# AIRZAI_BASE_BD_REVA_Sheet1.net
KiCad netlist of a schematic drawn in Altium Designer
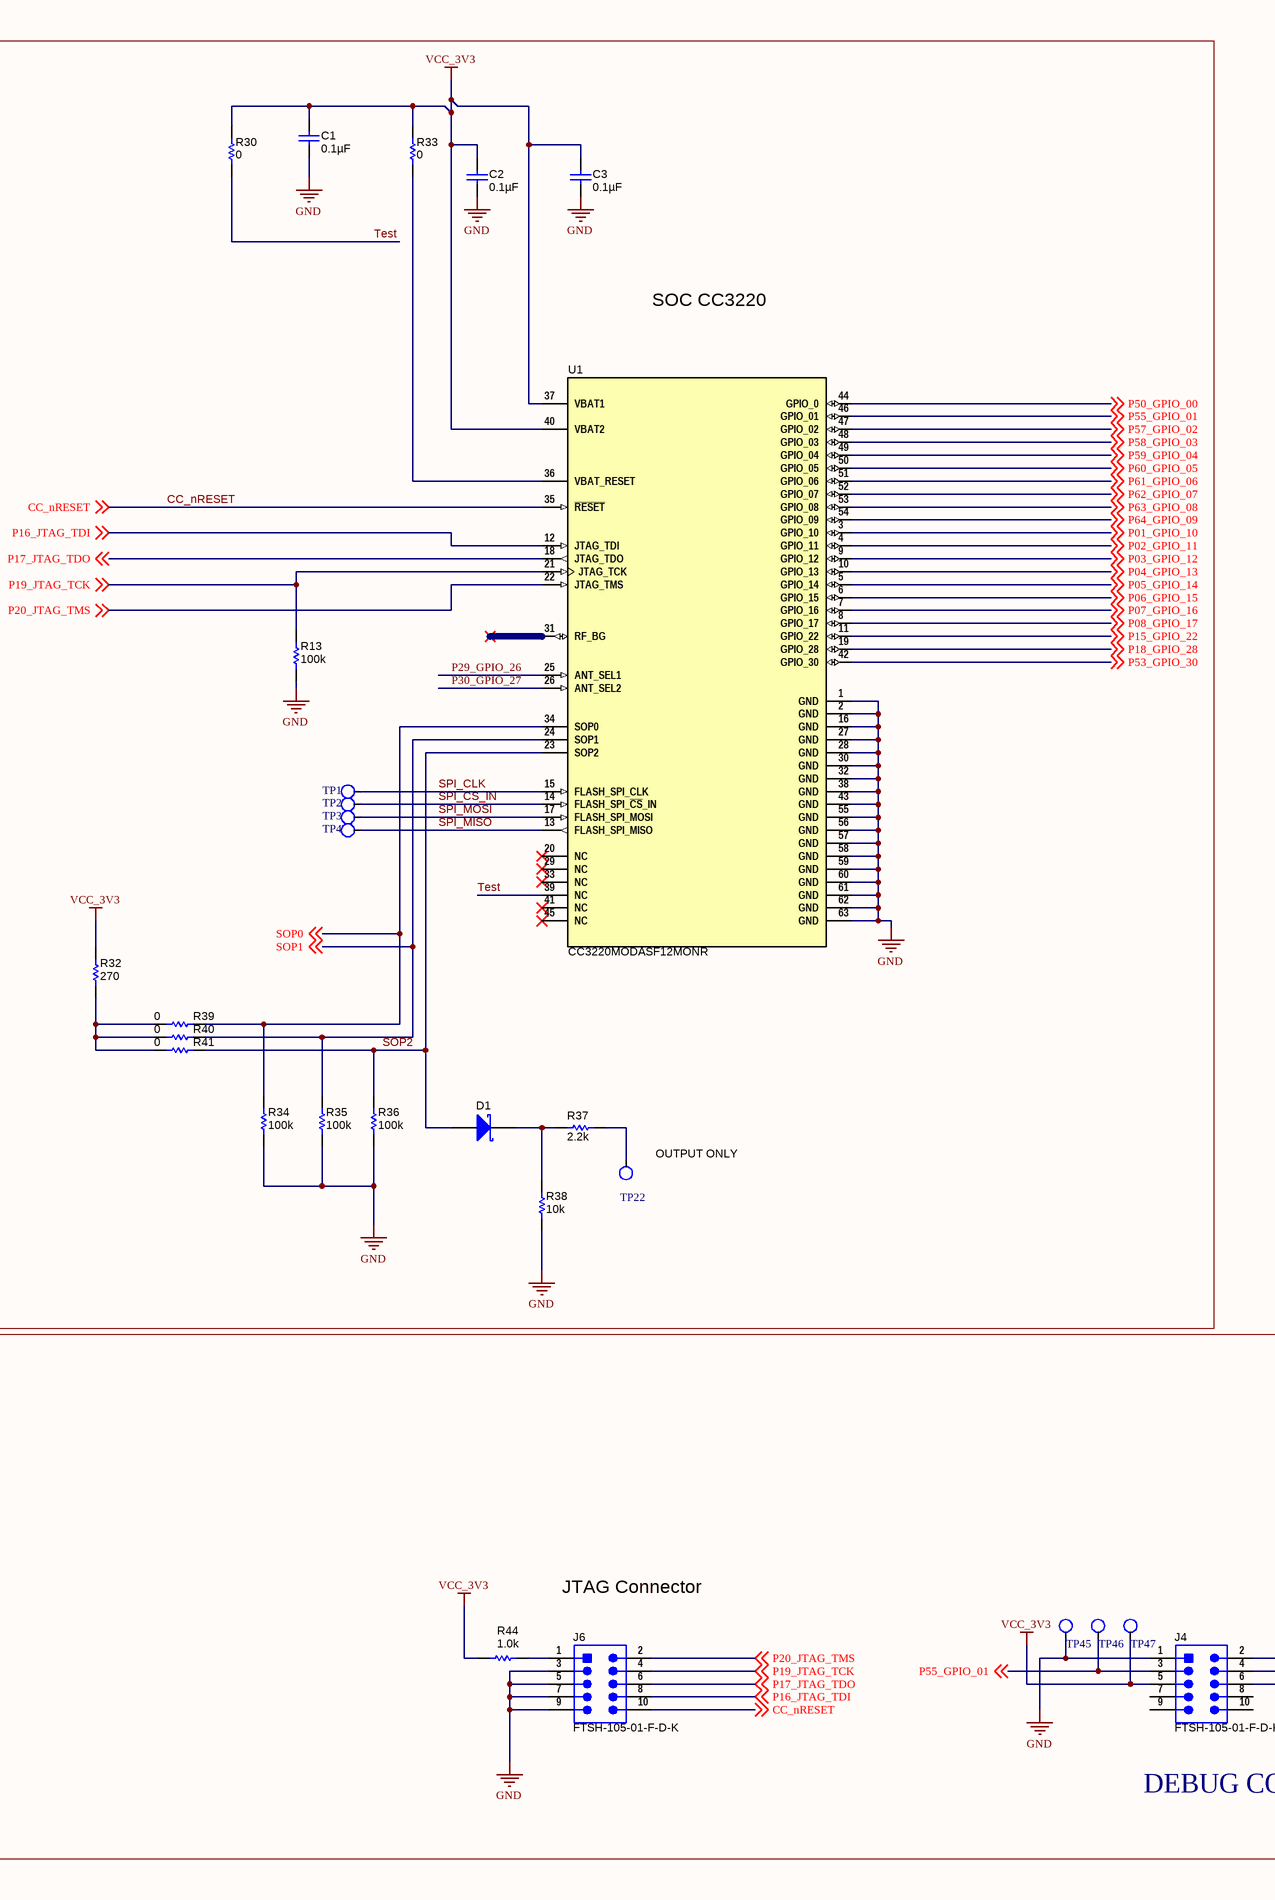
[diagram p0: AIRZAI_BASE_BD_REVA Sheet1.SchDoc, left]
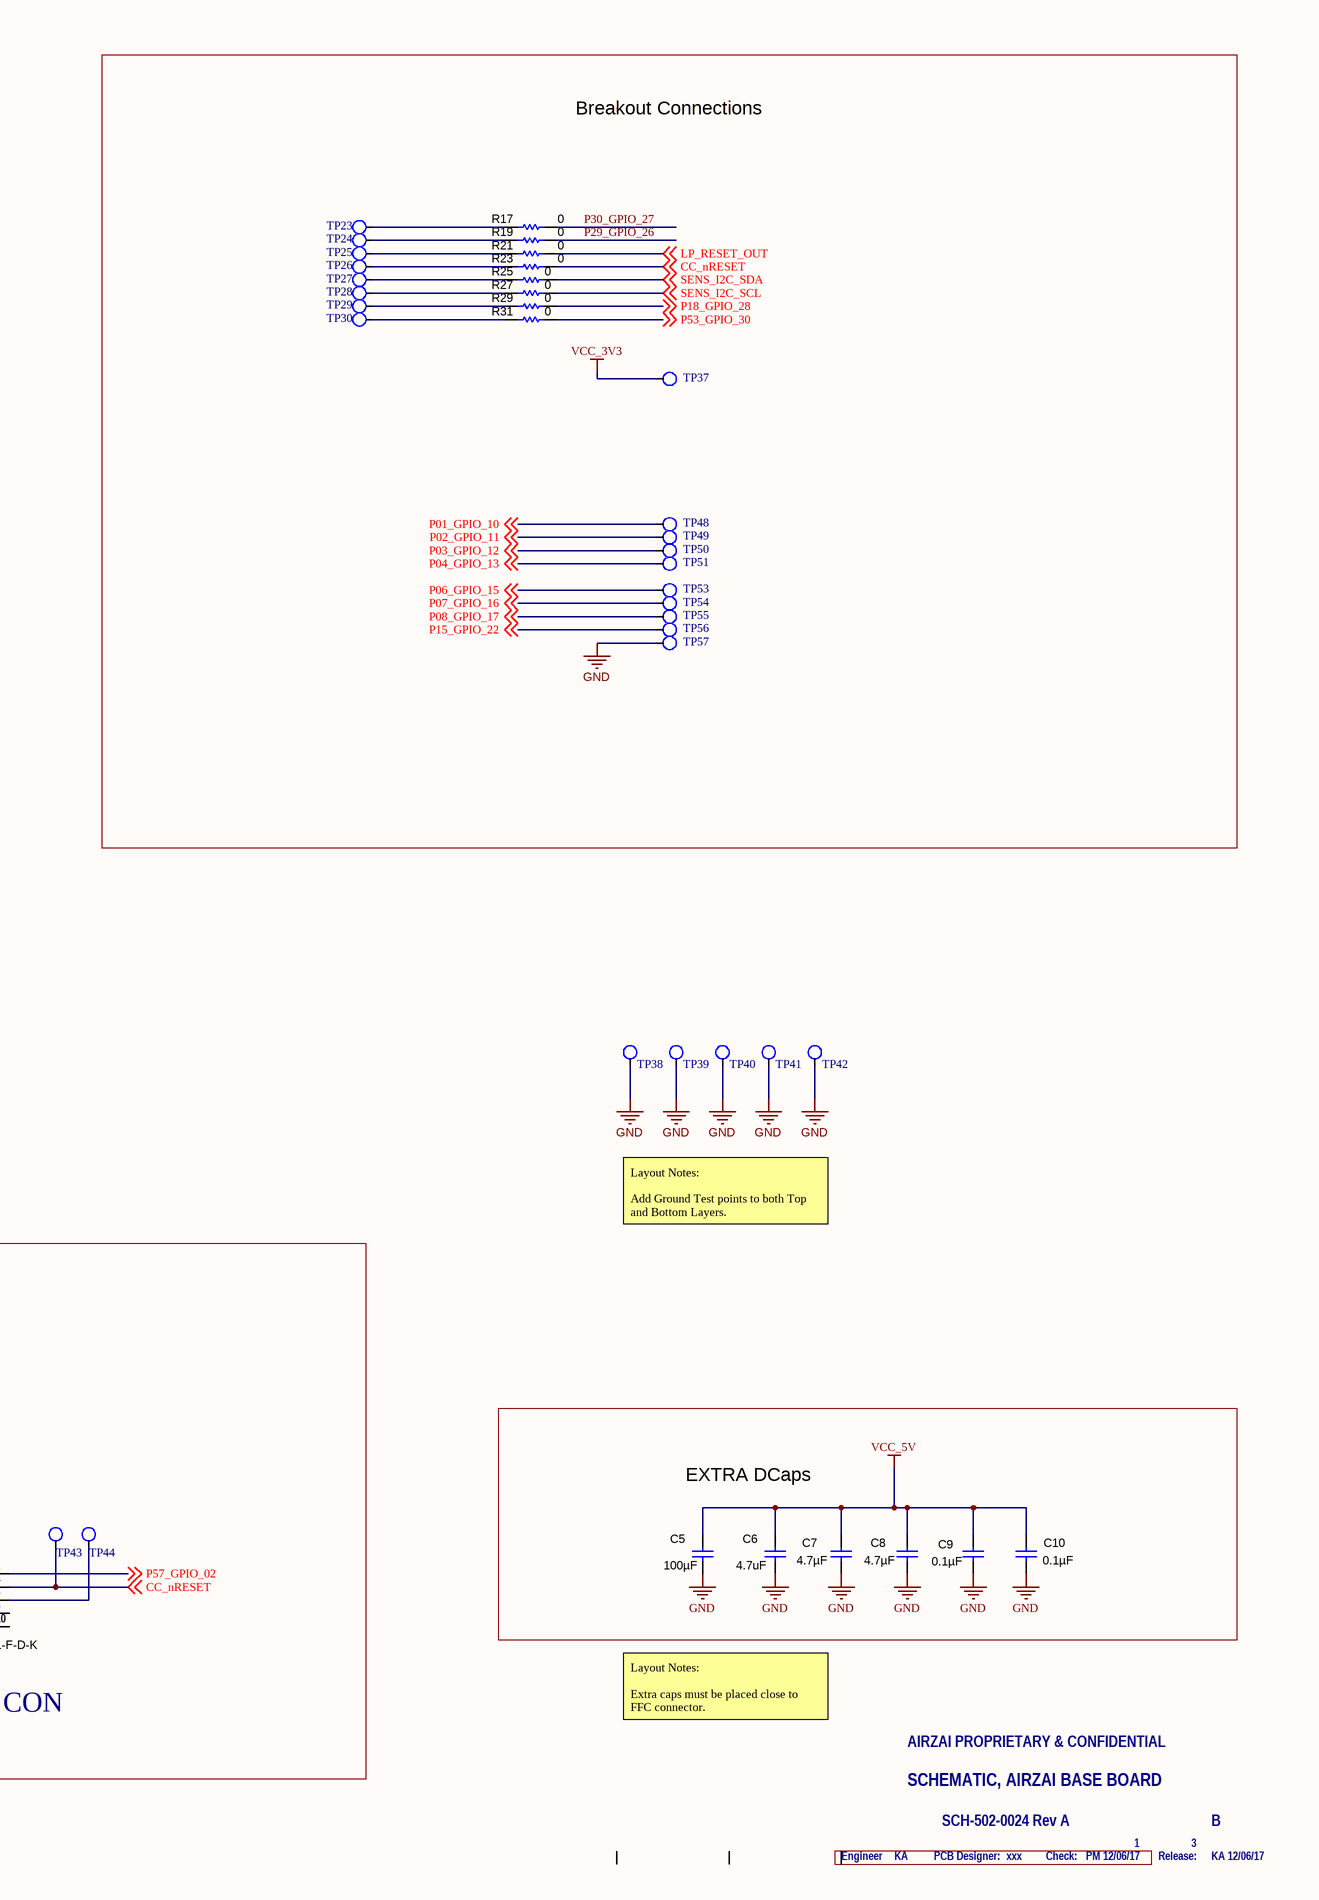
[diagram p1: AIRZAI_BASE_BD_REVA Sheet1.SchDoc, right]

(export (version "E")
  (design (tool "Eeschema 10.0.6"))
  (components
    (comp (ref "C1")
      (value "GRM155R61A104KA01D")
      (footprint "0402")
      (description "CAP, CERM, 0.1 µF, 10 V, +/- 10%, X5R, 0402")
      (fields
        (field (name "VALUEDISPLAYED") "0.1µF")
        (field (name "MANUFACTURER") "MuRata")
        (field (name "PUBLISHER") "Texas Instruments")
      )
      (libsource (lib "Capacitor_Ceramic") (part "GRM155R61A104KA01D"))
    )
    (comp (ref "C2")
      (value "GRM155R61A104KA01D")
      (footprint "0402")
      (description "CAP, CERM, 0.1 µF, 10 V, +/- 10%, X5R, 0402")
      (fields
        (field (name "VALUEDISPLAYED") "0.1µF")
        (field (name "MANUFACTURER") "MuRata")
        (field (name "PUBLISHER") "Texas Instruments")
      )
      (libsource (lib "Capacitor_Ceramic") (part "GRM155R61A104KA01D"))
    )
    (comp (ref "C3")
      (value "GRM155R61A104KA01D")
      (footprint "0402")
      (description "CAP, CERM, 0.1 µF, 10 V, +/- 10%, X5R, 0402")
      (fields
        (field (name "VALUEDISPLAYED") "0.1µF")
        (field (name "MANUFACTURER") "MuRata")
        (field (name "PUBLISHER") "Texas Instruments")
      )
      (libsource (lib "Capacitor_Ceramic") (part "GRM155R61A104KA01D"))
    )
    (comp (ref "C5")
      (value "GRM31CR60J107ME39L")
      (footprint "1206_180")
      (description "CAP, CERM, 100 µF, 6.3 V, +/- 20%, X5R, 1206")
      (fields
        (field (name "VALUEDISPLAYED") "100µF")
        (field (name "MANUFACTURER") "MuRata")
        (field (name "PUBLISHER") "Texas Instruments")
      )
      (libsource (lib "Capacitor_Ceramic") (part "GRM31CR60J107ME39L"))
    )
    (comp (ref "C6")
      (value "4.7uF")
      (footprint "SM0402_BTD.1SM_ACT_H55_CAP_WSS")
      (description "CAP, CERM, 4.7 µF, 6.3 V, +/- 20%, X5R, 0402")
      (fields (field (name "PARTNUMBER") "C1005X5R0J475M050BC") (field (name "MANUFACTURER") "TDK"))
      (libsource (lib "Capacitor_Ceramic") (part "C1005X5R0J475M050BC"))
    )
    (comp (ref "C7")
      (value "C1005X5R0J475M050BC")
      (footprint "SM0402_BTD.1SM_ACT_H55_CAP_WSS")
      (description "CAP, CERM, 4.7 µF, 6.3 V, +/- 20%, X5R, 0402")
      (fields
        (field (name "VALUEDISPLAYED") "4.7µF")
        (field (name "MANUFACTURER") "TDK")
        (field (name "PUBLISHER") "Texas Instruments")
      )
      (libsource (lib "Capacitor_Ceramic") (part "C1005X5R0J475M050BC"))
    )
    (comp (ref "C8")
      (value "C1005X5R0J475M050BC")
      (footprint "SM0402_BTD.1SM_ACT_H55_CAP_WSS")
      (description "CAP, CERM, 4.7 µF, 6.3 V, +/- 20%, X5R, 0402")
      (fields
        (field (name "VALUEDISPLAYED") "4.7µF")
        (field (name "MANUFACTURER") "TDK")
        (field (name "PUBLISHER") "Texas Instruments")
      )
      (libsource (lib "Capacitor_Ceramic") (part "C1005X5R0J475M050BC"))
    )
    (comp (ref "C9")
      (value "C1005X5R1A104K050BA")
      (footprint "SM0402_BTD.1SM_ACT_H55_CAP_WSS")
      (description "CAP, CERM, 0.1 µF, 10 V, +/- 10%, X5R, 0402")
      (fields
        (field (name "VALUEDISPLAYED") "0.1µF")
        (field (name "MANUFACTURER") "TDK")
        (field (name "PUBLISHER") "Texas Instruments")
      )
      (libsource (lib "Capacitor_Ceramic") (part "C1005X5R1A104K050BA"))
    )
    (comp (ref "C10")
      (value "C1005X5R1A104K050BA")
      (footprint "SM0402_BTD.1SM_ACT_H55_CAP_WSS")
      (description "CAP, CERM, 0.1 µF, 10 V, +/- 10%, X5R, 0402")
      (fields
        (field (name "VALUEDISPLAYED") "0.1µF")
        (field (name "MANUFACTURER") "TDK")
        (field (name "PUBLISHER") "Texas Instruments")
      )
      (libsource (lib "Capacitor_Ceramic") (part "C1005X5R1A104K050BA"))
    )
    (comp (ref "D1")
      (value "CD0603-B00340")
      (footprint "Diode_0603")
      (description "Diode, Schottky, 45 V, 0.03 A, 0603 Diode")
      (fields (field (name "MANUFACTURER") "Bourns") (field (name "PUBLISHER") "Texas Instruments"))
      (libsource (lib "Diode") (part "CD0603-B00340"))
    )
    (comp (ref "J4")
      (value "FTSH-105-01-F-D-K")
      (footprint "Samtec_FTSH-105-01-x-D-K")
      (description "Header, 1.27 mm, 5x2, Gold, TH")
      (fields
        (field (name "MANUFACTURER") "Samtec")
        (field (name "SYMBOLCREATOR") "a0412235")
        (field (name "PUBLISHER") "Texas Instruments")
      )
      (libsource (lib "Connectors_Samtec") (part "FTSH-105-01-F-D-K"))
    )
    (comp (ref "J6")
      (value "FTSH-105-01-F-D-K")
      (footprint "Samtec_FTSH-105-01-x-D-K")
      (description "Header, 1.27 mm, 5x2, Gold, TH")
      (fields
        (field (name "MANUFACTURER") "Samtec")
        (field (name "SYMBOLCREATOR") "a0412235")
        (field (name "PUBLISHER") "Texas Instruments")
      )
      (libsource (lib "Connectors_Samtec") (part "FTSH-105-01-F-D-K"))
    )
    (comp (ref "R13")
      (value "CRCW0402100KJNED")
      (footprint "0402")
      (description "RES, 100 k, 5%, 0.063 W, 0402")
      (fields
        (field (name "VALUEDISPLAYED") "100k")
        (field (name "MANUFACTURER") "Vishay-Dale")
        (field (name "PUBLISHER") "Texas Instruments")
      )
      (libsource (lib "Resistor_0402") (part "CRCW0402100KJNED"))
    )
    (comp (ref "R17")
      (value "ERJ-2GE0R00X")
      (footprint "0402")
      (description "RES, 0, 5%, 0.063 W, 0402")
      (fields
        (field (name "VALUEDISPLAYED") "0")
        (field (name "MANUFACTURER") "Panasonic")
        (field (name "PUBLISHER") "Texas Instruments")
      )
      (libsource (lib "Resistor_0402") (part "ERJ-2GE0R00X"))
    )
    (comp (ref "R19")
      (value "ERJ-2GE0R00X")
      (footprint "0402")
      (description "RES, 0, 5%, 0.063 W, 0402")
      (fields
        (field (name "VALUEDISPLAYED") "0")
        (field (name "MANUFACTURER") "Panasonic")
        (field (name "PUBLISHER") "Texas Instruments")
      )
      (libsource (lib "Resistor_0402") (part "ERJ-2GE0R00X"))
    )
    (comp (ref "R21")
      (value "ERJ-2GE0R00X")
      (footprint "0402")
      (description "RES, 0, 5%, 0.063 W, 0402")
      (fields
        (field (name "VALUEDISPLAYED") "0")
        (field (name "MANUFACTURER") "Panasonic")
        (field (name "PUBLISHER") "Texas Instruments")
      )
      (libsource (lib "Resistor_0402") (part "ERJ-2GE0R00X"))
    )
    (comp (ref "R23")
      (value "ERJ-2GE0R00X")
      (footprint "0402")
      (description "RES, 0, 5%, 0.063 W, 0402")
      (fields
        (field (name "VALUEDISPLAYED") "0")
        (field (name "MANUFACTURER") "Panasonic")
        (field (name "PUBLISHER") "Texas Instruments")
      )
      (libsource (lib "Resistor_0402") (part "ERJ-2GE0R00X"))
    )
    (comp (ref "R25")
      (value "ERJ-2GE0R00X")
      (footprint "0402")
      (description "RES, 0, 5%, 0.063 W, 0402")
      (fields
        (field (name "VALUEDISPLAYED") "0")
        (field (name "MANUFACTURER") "Panasonic")
        (field (name "PUBLISHER") "Texas Instruments")
      )
      (libsource (lib "Resistor_0402") (part "ERJ-2GE0R00X"))
    )
    (comp (ref "R27")
      (value "ERJ-2GE0R00X")
      (footprint "0402")
      (description "RES, 0, 5%, 0.063 W, 0402")
      (fields
        (field (name "VALUEDISPLAYED") "0")
        (field (name "MANUFACTURER") "Panasonic")
        (field (name "PUBLISHER") "Texas Instruments")
      )
      (libsource (lib "Resistor_0402") (part "ERJ-2GE0R00X"))
    )
    (comp (ref "R29")
      (value "ERJ-2GE0R00X")
      (footprint "0402")
      (description "RES, 0, 5%, 0.063 W, 0402")
      (fields
        (field (name "VALUEDISPLAYED") "0")
        (field (name "MANUFACTURER") "Panasonic")
        (field (name "PUBLISHER") "Texas Instruments")
      )
      (libsource (lib "Resistor_0402") (part "ERJ-2GE0R00X"))
    )
    (comp (ref "R30")
      (value "RC0603JR-070RL")
      (footprint "0603")
      (description "RES, 0, 5%, 0.1 W, 0603")
      (fields
        (field (name "VALUEDISPLAYED") "0")
        (field (name "MANUFACTURER") "Yageo")
        (field (name "TOLERANCE") "1%")
      )
      (libsource (lib "Resistor_0402") (part "ERJ-2GE0R00X"))
    )
    (comp (ref "R31")
      (value "ERJ-2GE0R00X")
      (footprint "0402")
      (description "RES, 0, 5%, 0.063 W, 0402")
      (fields
        (field (name "VALUEDISPLAYED") "0")
        (field (name "MANUFACTURER") "Panasonic")
        (field (name "PUBLISHER") "Texas Instruments")
      )
      (libsource (lib "Resistor_0402") (part "ERJ-2GE0R00X"))
    )
    (comp (ref "R32")
      (value "CRCW0402270RJNED")
      (footprint "0402")
      (description "RES, 270, 5%, 0.063 W, 0402")
      (fields
        (field (name "VALUEDISPLAYED") "270")
        (field (name "MANUFACTURER") "Vishay-Dale")
        (field (name "PUBLISHER") "Texas Instruments")
      )
      (libsource (lib "Resistor_0402") (part "CRCW0402270RJNED"))
    )
    (comp (ref "R33")
      (value "RC0603JR-070RL")
      (footprint "0603")
      (description "RES, 0, 5%, 0.1 W, 0603")
      (fields
        (field (name "VALUEDISPLAYED") "0")
        (field (name "MANUFACTURER") "Yageo")
        (field (name "TOLERANCE") "1%")
      )
      (libsource (lib "Resistor_0402") (part "ERJ-2GE0R00X"))
    )
    (comp (ref "R34")
      (value "CRCW0402100KJNED")
      (footprint "0402")
      (description "RES, 100 k, 5%, 0.063 W, 0402")
      (fields
        (field (name "VALUEDISPLAYED") "100k")
        (field (name "MANUFACTURER") "Vishay-Dale")
        (field (name "PUBLISHER") "Texas Instruments")
      )
      (libsource (lib "Resistor_0402") (part "CRCW0402100KJNED"))
    )
    (comp (ref "R35")
      (value "CRCW0402100KJNED")
      (footprint "0402")
      (description "RES, 100 k, 5%, 0.063 W, 0402")
      (fields
        (field (name "VALUEDISPLAYED") "100k")
        (field (name "MANUFACTURER") "Vishay-Dale")
        (field (name "PUBLISHER") "Texas Instruments")
      )
      (libsource (lib "Resistor_0402") (part "CRCW0402100KJNED"))
    )
    (comp (ref "R36")
      (value "CRCW0402100KJNED")
      (footprint "0402")
      (description "RES, 100 k, 5%, 0.063 W, 0402")
      (fields
        (field (name "VALUEDISPLAYED") "100k")
        (field (name "MANUFACTURER") "Vishay-Dale")
        (field (name "PUBLISHER") "Texas Instruments")
      )
      (libsource (lib "Resistor_0402") (part "CRCW0402100KJNED"))
    )
    (comp (ref "R37")
      (value "CRCW04022K20JNED")
      (footprint "0402")
      (description "RES, 2.2 k, 5%, 0.063 W, 0402")
      (fields
        (field (name "VALUEDISPLAYED") "2.2k")
        (field (name "MANUFACTURER") "Vishay-Dale")
        (field (name "PUBLISHER") "Texas Instruments")
      )
      (libsource (lib "Resistor_0402") (part "CRCW04022K20JNED"))
    )
    (comp (ref "R38")
      (value "CRCW040210K0JNED")
      (footprint "0402")
      (description "RES, 10 k, 5%, 0.063 W, 0402")
      (fields
        (field (name "VALUEDISPLAYED") "10k")
        (field (name "MANUFACTURER") "Vishay-Dale")
        (field (name "PUBLISHER") "Texas Instruments")
      )
      (libsource (lib "Resistor_0402") (part "CRCW040210K0JNED"))
    )
    (comp (ref "R39")
      (value "RC0603JR-070RL")
      (footprint "0603")
      (description "RES, 0, 5%, 0.1 W, 0603")
      (fields
        (field (name "VALUEDISPLAYED") "0")
        (field (name "MANUFACTURER") "Yageo")
        (field (name "TOLERANCE") "1%")
      )
      (libsource (lib "Resistor_0402") (part "ERJ-2GE0R00X"))
    )
    (comp (ref "R40")
      (value "RC0603JR-070RL")
      (footprint "0603")
      (description "RES, 0, 5%, 0.1 W, 0603")
      (fields
        (field (name "VALUEDISPLAYED") "0")
        (field (name "MANUFACTURER") "Yageo")
        (field (name "TOLERANCE") "1%")
      )
      (libsource (lib "Resistor_0402") (part "ERJ-2GE0R00X"))
    )
    (comp (ref "R41")
      (value "RC0603JR-070RL")
      (footprint "0603")
      (description "RES, 0, 5%, 0.1 W, 0603")
      (fields
        (field (name "VALUEDISPLAYED") "0")
        (field (name "MANUFACTURER") "Yageo")
        (field (name "TOLERANCE") "1%")
      )
      (libsource (lib "Resistor_0402") (part "ERJ-2GE0R00X"))
    )
    (comp (ref "R44")
      (value "CRCW04021K00JNED")
      (footprint "0402")
      (description "RES, 1.0 k, 5%, 0.063 W, 0402")
      (fields
        (field (name "VALUEDISPLAYED") "1.0k")
        (field (name "MANUFACTURER") "Vishay-Dale")
        (field (name "PUBLISHER") "Texas Instruments")
      )
      (libsource (lib "Resistor_0402") (part "CRCW04021K00JNED"))
    )
    (comp (ref "TP1")
      (value "WIREPT")
      (footprint "TP_0.9MM")
      (libsource (lib "EAGLE_CAD_Library") (part "WIREPT"))
    )
    (comp (ref "TP2")
      (value "WIREPT")
      (footprint "TP_0.9MM")
      (libsource (lib "EAGLE_CAD_Library") (part "WIREPT"))
    )
    (comp (ref "TP3")
      (value "WIREPT")
      (footprint "TP_0.9MM")
      (libsource (lib "EAGLE_CAD_Library") (part "WIREPT"))
    )
    (comp (ref "TP4")
      (value "WIREPT")
      (footprint "TP_0.9MM")
      (libsource (lib "EAGLE_CAD_Library") (part "WIREPT"))
    )
    (comp (ref "TP22")
      (value "WIREPT")
      (footprint "TP_0.9MM")
      (libsource (lib "EAGLE_CAD_Library") (part "WIREPT"))
    )
    (comp (ref "TP23")
      (value "WIREPT")
      (footprint "TP_0.9MM")
      (libsource (lib "EAGLE_CAD_Library") (part "WIREPT"))
    )
    (comp (ref "TP24")
      (value "WIREPT")
      (footprint "TP_0.9MM")
      (libsource (lib "EAGLE_CAD_Library") (part "WIREPT"))
    )
    (comp (ref "TP25")
      (value "WIREPT")
      (footprint "TP_0.9MM")
      (libsource (lib "EAGLE_CAD_Library") (part "WIREPT"))
    )
    (comp (ref "TP26")
      (value "WIREPT")
      (footprint "TP_0.9MM")
      (libsource (lib "EAGLE_CAD_Library") (part "WIREPT"))
    )
    (comp (ref "TP27")
      (value "WIREPT")
      (footprint "TP_0.9MM")
      (libsource (lib "EAGLE_CAD_Library") (part "WIREPT"))
    )
    (comp (ref "TP28")
      (value "WIREPT")
      (footprint "TP_0.9MM")
      (libsource (lib "EAGLE_CAD_Library") (part "WIREPT"))
    )
    (comp (ref "TP29")
      (value "WIREPT")
      (footprint "TP_0.9MM")
      (libsource (lib "EAGLE_CAD_Library") (part "WIREPT"))
    )
    (comp (ref "TP30")
      (value "WIREPT")
      (footprint "TP_0.9MM")
      (libsource (lib "EAGLE_CAD_Library") (part "WIREPT"))
    )
    (comp (ref "TP37")
      (value "WIREPT")
      (footprint "TP_0.9MM")
      (libsource (lib "EAGLE_CAD_Library") (part "WIREPT"))
    )
    (comp (ref "TP38")
      (value "WIREPT")
      (footprint "TP_0.9MM")
      (libsource (lib "EAGLE_CAD_Library") (part "WIREPT"))
    )
    (comp (ref "TP39")
      (value "WIREPT")
      (footprint "TP_0.9MM")
      (libsource (lib "EAGLE_CAD_Library") (part "WIREPT"))
    )
    (comp (ref "TP40")
      (value "WIREPT")
      (footprint "TP_0.9MM")
      (libsource (lib "EAGLE_CAD_Library") (part "WIREPT"))
    )
    (comp (ref "TP41")
      (value "WIREPT")
      (footprint "TP_0.9MM")
      (libsource (lib "EAGLE_CAD_Library") (part "WIREPT"))
    )
    (comp (ref "TP42")
      (value "WIREPT")
      (footprint "TP_0.9MM")
      (libsource (lib "EAGLE_CAD_Library") (part "WIREPT"))
    )
    (comp (ref "TP43")
      (value "WIREPT")
      (footprint "TP_0.9MM")
      (libsource (lib "EAGLE_CAD_Library") (part "WIREPT"))
    )
    (comp (ref "TP44")
      (value "WIREPT")
      (footprint "TP_0.9MM")
      (libsource (lib "EAGLE_CAD_Library") (part "WIREPT"))
    )
    (comp (ref "TP45")
      (value "WIREPT")
      (footprint "TP_0.9MM")
      (libsource (lib "EAGLE_CAD_Library") (part "WIREPT"))
    )
    (comp (ref "TP46")
      (value "WIREPT")
      (footprint "TP_0.9MM")
      (libsource (lib "EAGLE_CAD_Library") (part "WIREPT"))
    )
    (comp (ref "TP47")
      (value "WIREPT")
      (footprint "TP_0.9MM")
      (libsource (lib "EAGLE_CAD_Library") (part "WIREPT"))
    )
    (comp (ref "TP48")
      (value "WIREPT")
      (footprint "TP_0.9MM")
      (libsource (lib "EAGLE_CAD_Library") (part "WIREPT"))
    )
    (comp (ref "TP49")
      (value "WIREPT")
      (footprint "TP_0.9MM")
      (libsource (lib "EAGLE_CAD_Library") (part "WIREPT"))
    )
    (comp (ref "TP50")
      (value "WIREPT")
      (footprint "TP_0.9MM")
      (libsource (lib "EAGLE_CAD_Library") (part "WIREPT"))
    )
    (comp (ref "TP51")
      (value "WIREPT")
      (footprint "TP_0.9MM")
      (libsource (lib "EAGLE_CAD_Library") (part "WIREPT"))
    )
    (comp (ref "TP53")
      (value "WIREPT")
      (footprint "TP_0.9MM")
      (libsource (lib "EAGLE_CAD_Library") (part "WIREPT"))
    )
    (comp (ref "TP54")
      (value "WIREPT")
      (footprint "TP_0.9MM")
      (libsource (lib "EAGLE_CAD_Library") (part "WIREPT"))
    )
    (comp (ref "TP55")
      (value "WIREPT")
      (footprint "TP_0.9MM")
      (libsource (lib "EAGLE_CAD_Library") (part "WIREPT"))
    )
    (comp (ref "TP56")
      (value "WIREPT")
      (footprint "TP_0.9MM")
      (libsource (lib "EAGLE_CAD_Library") (part "WIREPT"))
    )
    (comp (ref "TP57")
      (value "WIREPT")
      (footprint "TP_0.9MM")
      (libsource (lib "EAGLE_CAD_Library") (part "WIREPT"))
    )
    (comp (ref "U1")
      (value "CC3220MODASF12MONR")
      (footprint "MON0063A")
      (fields
        (field (name "ALTERNATE PARTNUMBER") "XCC3220MODASF12MONR")
        (field (name "MANUFACTURER") "Texas Instruments")
        (field (name "SYMBOLCREATOR") "Altium")
        (field (name "PUBLISHER") "Texas Instruments")
      )
      (libsource (lib "TI_Pre_RTM") (part "CC3220MODASF12MONR"))
    )
  )
  (nets
    (net (code "1") (name "/P29_GPIO_26") (class "Default")
      (node (ref "R19") (pin "2") (pinfunction "2_2") (pintype "passive"))
      (node (ref "U1") (pin "25") (pinfunction "ANT_SEL1_25") (pintype "input"))
    )
    (net (code "2") (name "/P30_GPIO_27") (class "Default")
      (node (ref "R17") (pin "2") (pinfunction "2_2") (pintype "passive"))
      (node (ref "U1") (pin "26") (pinfunction "ANT_SEL2_26") (pintype "input"))
    )
    (net (code "3") (name "/SOP2") (class "Default")
      (node (ref "D1") (pin "2") (pinfunction "A_2") (pintype "passive"))
      (node (ref "R36") (pin "1") (pinfunction "1_1") (pintype "passive"))
      (node (ref "R41") (pin "1") (pinfunction "1_1") (pintype "passive"))
      (node (ref "U1") (pin "23") (pinfunction "SOP2_23") (pintype "passive"))
    )
    (net (code "4") (name "/SPI_CLK") (class "Default")
      (node (ref "TP1") (pin "1") (pinfunction "1_1") (pintype "passive"))
      (node (ref "U1") (pin "15") (pinfunction "FLASH_SPI_CLK_15") (pintype "input"))
    )
    (net (code "5") (name "/SPI_CS_IN") (class "Default")
      (node (ref "TP2") (pin "1") (pinfunction "1_1") (pintype "passive"))
      (node (ref "U1") (pin "14") (pinfunction "FLASH_SPI_~{CS}_IN_14") (pintype "input"))
    )
    (net (code "6") (name "/SPI_MISO") (class "Default")
      (node (ref "TP4") (pin "1") (pinfunction "1_1") (pintype "passive"))
      (node (ref "U1") (pin "13") (pinfunction "FLASH_SPI_MISO_13") (pintype "output"))
    )
    (net (code "7") (name "/SPI_MOSI") (class "Default")
      (node (ref "TP3") (pin "1") (pinfunction "1_1") (pintype "passive"))
      (node (ref "U1") (pin "17") (pinfunction "FLASH_SPI_MOSI_17") (pintype "input"))
    )
    (net (code "8") (name "/Test") (class "Default")
      (node (ref "R30") (pin "1") (pinfunction "1_1") (pintype "passive"))
      (node (ref "U1") (pin "39") (pinfunction "NC_39") (pintype "passive"))
    )
    (net (code "9") (name "CC_nRESET") (class "Default")
      (node (ref "J4") (pin "4") (pinfunction "4_4") (pintype "passive"))
      (node (ref "J6") (pin "10") (pinfunction "10_10") (pintype "passive"))
      (node (ref "R23") (pin "2") (pinfunction "2_2") (pintype "passive"))
      (node (ref "TP43") (pin "1") (pinfunction "1_1") (pintype "passive"))
      (node (ref "U1") (pin "35") (pinfunction "RESET_35") (pintype "input"))
    )
    (net (code "10") (name "GND") (class "Default")
      (node (ref "C1") (pin "2") (pinfunction "2_2") (pintype "passive"))
      (node (ref "C10") (pin "2") (pinfunction "2_2") (pintype "passive"))
      (node (ref "C2") (pin "2") (pinfunction "2_2") (pintype "passive"))
      (node (ref "C3") (pin "2") (pinfunction "2_2") (pintype "passive"))
      (node (ref "C5") (pin "2") (pinfunction "2_2") (pintype "passive"))
      (node (ref "C6") (pin "2") (pinfunction "2_2") (pintype "passive"))
      (node (ref "C7") (pin "2") (pinfunction "2_2") (pintype "passive"))
      (node (ref "C8") (pin "2") (pinfunction "2_2") (pintype "passive"))
      (node (ref "C9") (pin "2") (pinfunction "2_2") (pintype "passive"))
      (node (ref "J4") (pin "1") (pinfunction "1_1") (pintype "passive"))
      (node (ref "J6") (pin "3") (pinfunction "3_3") (pintype "passive"))
      (node (ref "J6") (pin "5") (pinfunction "5_5") (pintype "passive"))
      (node (ref "J6") (pin "7") (pinfunction "7_7") (pintype "passive"))
      (node (ref "J6") (pin "9") (pinfunction "9_9") (pintype "passive"))
      (node (ref "R13") (pin "2") (pinfunction "2_2") (pintype "passive"))
      (node (ref "R34") (pin "1") (pinfunction "1_1") (pintype "passive"))
      (node (ref "R35") (pin "2") (pinfunction "2_2") (pintype "passive"))
      (node (ref "R36") (pin "2") (pinfunction "2_2") (pintype "passive"))
      (node (ref "R38") (pin "2") (pinfunction "2_2") (pintype "passive"))
      (node (ref "TP38") (pin "1") (pinfunction "1_1") (pintype "passive"))
      (node (ref "TP39") (pin "1") (pinfunction "1_1") (pintype "passive"))
      (node (ref "TP40") (pin "1") (pinfunction "1_1") (pintype "passive"))
      (node (ref "TP41") (pin "1") (pinfunction "1_1") (pintype "passive"))
      (node (ref "TP42") (pin "1") (pinfunction "1_1") (pintype "passive"))
      (node (ref "TP45") (pin "1") (pinfunction "1_1") (pintype "passive"))
      (node (ref "TP57") (pin "1") (pinfunction "1_1") (pintype "passive"))
      (node (ref "U1") (pin "1") (pinfunction "GND_1") (pintype "power_in"))
      (node (ref "U1") (pin "16") (pinfunction "GND_16") (pintype "power_in"))
      (node (ref "U1") (pin "2") (pinfunction "GND_2") (pintype "power_in"))
      (node (ref "U1") (pin "27") (pinfunction "GND_27") (pintype "power_in"))
      (node (ref "U1") (pin "28") (pinfunction "GND_28") (pintype "power_in"))
      (node (ref "U1") (pin "30") (pinfunction "GND_30") (pintype "power_in"))
      (node (ref "U1") (pin "32") (pinfunction "GND_32") (pintype "power_in"))
      (node (ref "U1") (pin "38") (pinfunction "GND_38") (pintype "power_in"))
      (node (ref "U1") (pin "43") (pinfunction "GND_43") (pintype "power_in"))
      (node (ref "U1") (pin "55") (pinfunction "GND_55") (pintype "power_in"))
      (node (ref "U1") (pin "56") (pinfunction "GND_56") (pintype "power_in"))
      (node (ref "U1") (pin "57") (pinfunction "GND_57") (pintype "power_in"))
      (node (ref "U1") (pin "58") (pinfunction "GND_58") (pintype "power_in"))
      (node (ref "U1") (pin "59") (pinfunction "GND_59") (pintype "power_in"))
      (node (ref "U1") (pin "60") (pinfunction "GND_60") (pintype "power_in"))
      (node (ref "U1") (pin "61") (pinfunction "GND_61") (pintype "power_in"))
      (node (ref "U1") (pin "62") (pinfunction "GND_62") (pintype "power_in"))
      (node (ref "U1") (pin "63") (pinfunction "GND_63") (pintype "power_in"))
    )
    (net (code "11") (name "LP_RESET_OUT") (class "Default")
      (node (ref "R21") (pin "2") (pinfunction "2_2") (pintype "passive"))
    )
    (net (code "12") (name "Net-(D1-K)") (class "Default")
      (node (ref "D1") (pin "1") (pinfunction "K_1") (pintype "passive"))
      (node (ref "R37") (pin "1") (pinfunction "1_1") (pintype "passive"))
      (node (ref "R38") (pin "1") (pinfunction "1_1") (pintype "passive"))
    )
    (net (code "13") (name "Net-(J4-Pad6)") (class "Default")
      (node (ref "J4") (pin "6") (pinfunction "6_6") (pintype "passive"))
      (node (ref "TP44") (pin "1") (pinfunction "1_1") (pintype "passive"))
    )
    (net (code "14") (name "Net-(J6-Pad1)") (class "Default")
      (node (ref "J6") (pin "1") (pinfunction "1_1") (pintype "passive"))
      (node (ref "R44") (pin "2") (pinfunction "2_2") (pintype "passive"))
    )
    (net (code "15") (name "Net-(R17-Pad1)") (class "Default")
      (node (ref "R17") (pin "1") (pinfunction "1_1") (pintype "passive"))
      (node (ref "TP23") (pin "1") (pinfunction "1_1") (pintype "passive"))
    )
    (net (code "16") (name "Net-(R19-Pad1)") (class "Default")
      (node (ref "R19") (pin "1") (pinfunction "1_1") (pintype "passive"))
      (node (ref "TP24") (pin "1") (pinfunction "1_1") (pintype "passive"))
    )
    (net (code "17") (name "Net-(R21-Pad1)") (class "Default")
      (node (ref "R21") (pin "1") (pinfunction "1_1") (pintype "passive"))
      (node (ref "TP25") (pin "1") (pinfunction "1_1") (pintype "passive"))
    )
    (net (code "18") (name "Net-(R23-Pad1)") (class "Default")
      (node (ref "R23") (pin "1") (pinfunction "1_1") (pintype "passive"))
      (node (ref "TP26") (pin "1") (pinfunction "1_1") (pintype "passive"))
    )
    (net (code "19") (name "Net-(R25-Pad1)") (class "Default")
      (node (ref "R25") (pin "1") (pinfunction "1_1") (pintype "passive"))
      (node (ref "TP27") (pin "1") (pinfunction "1_1") (pintype "passive"))
    )
    (net (code "20") (name "Net-(R27-Pad1)") (class "Default")
      (node (ref "R27") (pin "1") (pinfunction "1_1") (pintype "passive"))
      (node (ref "TP28") (pin "1") (pinfunction "1_1") (pintype "passive"))
    )
    (net (code "21") (name "Net-(R29-Pad1)") (class "Default")
      (node (ref "R29") (pin "1") (pinfunction "1_1") (pintype "passive"))
      (node (ref "TP29") (pin "1") (pinfunction "1_1") (pintype "passive"))
    )
    (net (code "22") (name "Net-(R31-Pad1)") (class "Default")
      (node (ref "R31") (pin "1") (pinfunction "1_1") (pintype "passive"))
      (node (ref "TP30") (pin "1") (pinfunction "1_1") (pintype "passive"))
    )
    (net (code "23") (name "Net-(R32-Pad2)") (class "Default")
      (node (ref "R32") (pin "2") (pinfunction "2_2") (pintype "passive"))
      (node (ref "R39") (pin "2") (pinfunction "2_2") (pintype "passive"))
      (node (ref "R40") (pin "2") (pinfunction "2_2") (pintype "passive"))
      (node (ref "R41") (pin "2") (pinfunction "2_2") (pintype "passive"))
    )
    (net (code "24") (name "Net-(R37-Pad2)") (class "Default")
      (node (ref "R37") (pin "2") (pinfunction "2_2") (pintype "passive"))
      (node (ref "TP22") (pin "1") (pinfunction "1_1") (pintype "passive"))
    )
    (net (code "25") (name "Net-(U1-VBAT_RESET)") (class "Default")
      (node (ref "R33") (pin "1") (pinfunction "1_1") (pintype "passive"))
      (node (ref "U1") (pin "36") (pinfunction "VBAT_RESET_36") (pintype "passive"))
    )
    (net (code "26") (name "P01_GPIO_10") (class "Default")
      (node (ref "TP48") (pin "1") (pinfunction "1_1") (pintype "passive"))
      (node (ref "U1") (pin "3") (pinfunction "GPIO_10_3") (pintype "bidirectional"))
    )
    (net (code "27") (name "P02_GPIO_11") (class "Default")
      (node (ref "TP49") (pin "1") (pinfunction "1_1") (pintype "passive"))
      (node (ref "U1") (pin "4") (pinfunction "GPIO_11_4") (pintype "bidirectional"))
    )
    (net (code "28") (name "P03_GPIO_12") (class "Default")
      (node (ref "TP50") (pin "1") (pinfunction "1_1") (pintype "passive"))
      (node (ref "U1") (pin "9") (pinfunction "GPIO_12_9") (pintype "bidirectional"))
    )
    (net (code "29") (name "P04_GPIO_13") (class "Default")
      (node (ref "TP51") (pin "1") (pinfunction "1_1") (pintype "passive"))
      (node (ref "U1") (pin "10") (pinfunction "GPIO_13_10") (pintype "bidirectional"))
    )
    (net (code "30") (name "P05_GPIO_14") (class "Default")
      (node (ref "U1") (pin "5") (pinfunction "GPIO_14_5") (pintype "bidirectional"))
    )
    (net (code "31") (name "P06_GPIO_15") (class "Default")
      (node (ref "TP53") (pin "1") (pinfunction "1_1") (pintype "passive"))
      (node (ref "U1") (pin "6") (pinfunction "GPIO_15_6") (pintype "bidirectional"))
    )
    (net (code "32") (name "P07_GPIO_16") (class "Default")
      (node (ref "TP54") (pin "1") (pinfunction "1_1") (pintype "passive"))
      (node (ref "U1") (pin "7") (pinfunction "GPIO_16_7") (pintype "bidirectional"))
    )
    (net (code "33") (name "P08_GPIO_17") (class "Default")
      (node (ref "TP55") (pin "1") (pinfunction "1_1") (pintype "passive"))
      (node (ref "U1") (pin "8") (pinfunction "GPIO_17_8") (pintype "bidirectional"))
    )
    (net (code "34") (name "P15_GPIO_22") (class "Default")
      (node (ref "TP56") (pin "1") (pinfunction "1_1") (pintype "passive"))
      (node (ref "U1") (pin "11") (pinfunction "GPIO_22_11") (pintype "bidirectional"))
    )
    (net (code "35") (name "P16_JTAG_TDI") (class "Default")
      (node (ref "J6") (pin "8") (pinfunction "8_8") (pintype "passive"))
      (node (ref "U1") (pin "12") (pinfunction "JTAG_TDI_12") (pintype "input"))
    )
    (net (code "36") (name "P17_JTAG_TDO") (class "Default")
      (node (ref "J6") (pin "6") (pinfunction "6_6") (pintype "passive"))
      (node (ref "U1") (pin "18") (pinfunction "JTAG_TDO_18") (pintype "output"))
    )
    (net (code "37") (name "P18_GPIO_28") (class "Default")
      (node (ref "R29") (pin "2") (pinfunction "2_2") (pintype "passive"))
      (node (ref "U1") (pin "19") (pinfunction "GPIO_28_19") (pintype "bidirectional"))
    )
    (net (code "38") (name "P19_JTAG_TCK") (class "Default")
      (node (ref "J6") (pin "4") (pinfunction "4_4") (pintype "passive"))
      (node (ref "R13") (pin "1") (pinfunction "1_1") (pintype "passive"))
      (node (ref "U1") (pin "21") (pinfunction "JTAG_TCK_21") (pintype "input"))
    )
    (net (code "39") (name "P20_JTAG_TMS") (class "Default")
      (node (ref "J6") (pin "2") (pinfunction "2_2") (pintype "passive"))
      (node (ref "U1") (pin "22") (pinfunction "JTAG_TMS_22") (pintype "input"))
    )
    (net (code "40") (name "P50_GPIO_00") (class "Default")
      (node (ref "U1") (pin "44") (pinfunction "GPIO_0_44") (pintype "bidirectional"))
    )
    (net (code "41") (name "P53_GPIO_30") (class "Default")
      (node (ref "R31") (pin "2") (pinfunction "2_2") (pintype "passive"))
      (node (ref "U1") (pin "42") (pinfunction "GPIO_30_42") (pintype "bidirectional"))
    )
    (net (code "42") (name "P55_GPIO_01") (class "Default")
      (node (ref "J4") (pin "3") (pinfunction "3_3") (pintype "passive"))
      (node (ref "TP46") (pin "1") (pinfunction "1_1") (pintype "passive"))
      (node (ref "U1") (pin "46") (pinfunction "GPIO_01_46") (pintype "bidirectional"))
    )
    (net (code "43") (name "P57_GPIO_02") (class "Default")
      (node (ref "J4") (pin "2") (pinfunction "2_2") (pintype "passive"))
      (node (ref "U1") (pin "47") (pinfunction "GPIO_02_47") (pintype "bidirectional"))
    )
    (net (code "44") (name "P58_GPIO_03") (class "Default")
      (node (ref "U1") (pin "48") (pinfunction "GPIO_03_48") (pintype "bidirectional"))
    )
    (net (code "45") (name "P59_GPIO_04") (class "Default")
      (node (ref "U1") (pin "49") (pinfunction "GPIO_04_49") (pintype "bidirectional"))
    )
    (net (code "46") (name "P60_GPIO_05") (class "Default")
      (node (ref "U1") (pin "50") (pinfunction "GPIO_05_50") (pintype "bidirectional"))
    )
    (net (code "47") (name "P61_GPIO_06") (class "Default")
      (node (ref "U1") (pin "51") (pinfunction "GPIO_06_51") (pintype "bidirectional"))
    )
    (net (code "48") (name "P62_GPIO_07") (class "Default")
      (node (ref "U1") (pin "52") (pinfunction "GPIO_07_52") (pintype "bidirectional"))
    )
    (net (code "49") (name "P63_GPIO_08") (class "Default")
      (node (ref "U1") (pin "53") (pinfunction "GPIO_08_53") (pintype "bidirectional"))
    )
    (net (code "50") (name "P64_GPIO_09") (class "Default")
      (node (ref "U1") (pin "54") (pinfunction "GPIO_09_54") (pintype "bidirectional"))
    )
    (net (code "51") (name "SENS_I2C_SCL") (class "Default")
      (node (ref "R27") (pin "2") (pinfunction "2_2") (pintype "passive"))
    )
    (net (code "52") (name "SENS_I2C_SDA") (class "Default")
      (node (ref "R25") (pin "2") (pinfunction "2_2") (pintype "passive"))
    )
    (net (code "53") (name "SOP0") (class "Default")
      (node (ref "R34") (pin "2") (pinfunction "2_2") (pintype "passive"))
      (node (ref "R39") (pin "1") (pinfunction "1_1") (pintype "passive"))
      (node (ref "U1") (pin "34") (pinfunction "SOP0_34") (pintype "passive"))
    )
    (net (code "54") (name "SOP1") (class "Default")
      (node (ref "R35") (pin "1") (pinfunction "1_1") (pintype "passive"))
      (node (ref "R40") (pin "1") (pinfunction "1_1") (pintype "passive"))
      (node (ref "U1") (pin "24") (pinfunction "SOP1_24") (pintype "passive"))
    )
    (net (code "55") (name "VCC_3V3") (class "Default")
      (node (ref "C1") (pin "1") (pinfunction "1_1") (pintype "passive"))
      (node (ref "C2") (pin "1") (pinfunction "1_1") (pintype "passive"))
      (node (ref "C3") (pin "1") (pinfunction "1_1") (pintype "passive"))
      (node (ref "J4") (pin "5") (pinfunction "5_5") (pintype "passive"))
      (node (ref "R30") (pin "2") (pinfunction "2_2") (pintype "passive"))
      (node (ref "R32") (pin "1") (pinfunction "1_1") (pintype "passive"))
      (node (ref "R33") (pin "2") (pinfunction "2_2") (pintype "passive"))
      (node (ref "R44") (pin "1") (pinfunction "1_1") (pintype "passive"))
      (node (ref "TP37") (pin "1") (pinfunction "1_1") (pintype "passive"))
      (node (ref "TP47") (pin "1") (pinfunction "1_1") (pintype "passive"))
      (node (ref "U1") (pin "37") (pinfunction "VBAT1_37") (pintype "power_in"))
      (node (ref "U1") (pin "40") (pinfunction "VBAT2_40") (pintype "power_in"))
    )
    (net (code "56") (name "VCC_5V") (class "Default")
      (node (ref "C10") (pin "1") (pinfunction "1_1") (pintype "passive"))
      (node (ref "C5") (pin "1") (pinfunction "1_1") (pintype "passive"))
      (node (ref "C6") (pin "1") (pinfunction "1_1") (pintype "passive"))
      (node (ref "C7") (pin "1") (pinfunction "1_1") (pintype "passive"))
      (node (ref "C8") (pin "1") (pinfunction "1_1") (pintype "passive"))
      (node (ref "C9") (pin "1") (pinfunction "1_1") (pintype "passive"))
    )
    (net (code "57") (name "unconnected-(J4-Pad7)") (class "Default")
      (node (ref "J4") (pin "7") (pinfunction "7_7") (pintype "passive"))
    )
    (net (code "58") (name "unconnected-(J4-Pad8)") (class "Default")
      (node (ref "J4") (pin "8") (pinfunction "8_8") (pintype "passive"))
    )
    (net (code "59") (name "unconnected-(J4-Pad9)") (class "Default")
      (node (ref "J4") (pin "9") (pinfunction "9_9") (pintype "passive"))
    )
    (net (code "60") (name "unconnected-(J4-Pad10)") (class "Default")
      (node (ref "J4") (pin "10") (pinfunction "10_10") (pintype "passive"))
    )
    (net (code "61") (name "unconnected-(U1-NC-Pad20)") (class "Default")
      (node (ref "U1") (pin "20") (pinfunction "NC_20") (pintype "passive+no_connect"))
    )
    (net (code "62") (name "unconnected-(U1-NC-Pad29)") (class "Default")
      (node (ref "U1") (pin "29") (pinfunction "NC_29") (pintype "passive+no_connect"))
    )
    (net (code "63") (name "unconnected-(U1-NC-Pad33)") (class "Default")
      (node (ref "U1") (pin "33") (pinfunction "NC_33") (pintype "passive+no_connect"))
    )
    (net (code "64") (name "unconnected-(U1-NC-Pad41)") (class "Default")
      (node (ref "U1") (pin "41") (pinfunction "NC_41") (pintype "passive+no_connect"))
    )
    (net (code "65") (name "unconnected-(U1-NC-Pad45)") (class "Default")
      (node (ref "U1") (pin "45") (pinfunction "NC_45") (pintype "passive+no_connect"))
    )
    (net (code "66") (name "unconnected-(U1-RF_BG-Pad31)") (class "Default")
      (node (ref "U1") (pin "31") (pinfunction "RF_BG_31") (pintype "bidirectional+no_connect"))
    )
  )
)
